# AfternoonCape_RevB1_TImux.net
KiCad netlist of a schematic drawn in Altium Designer
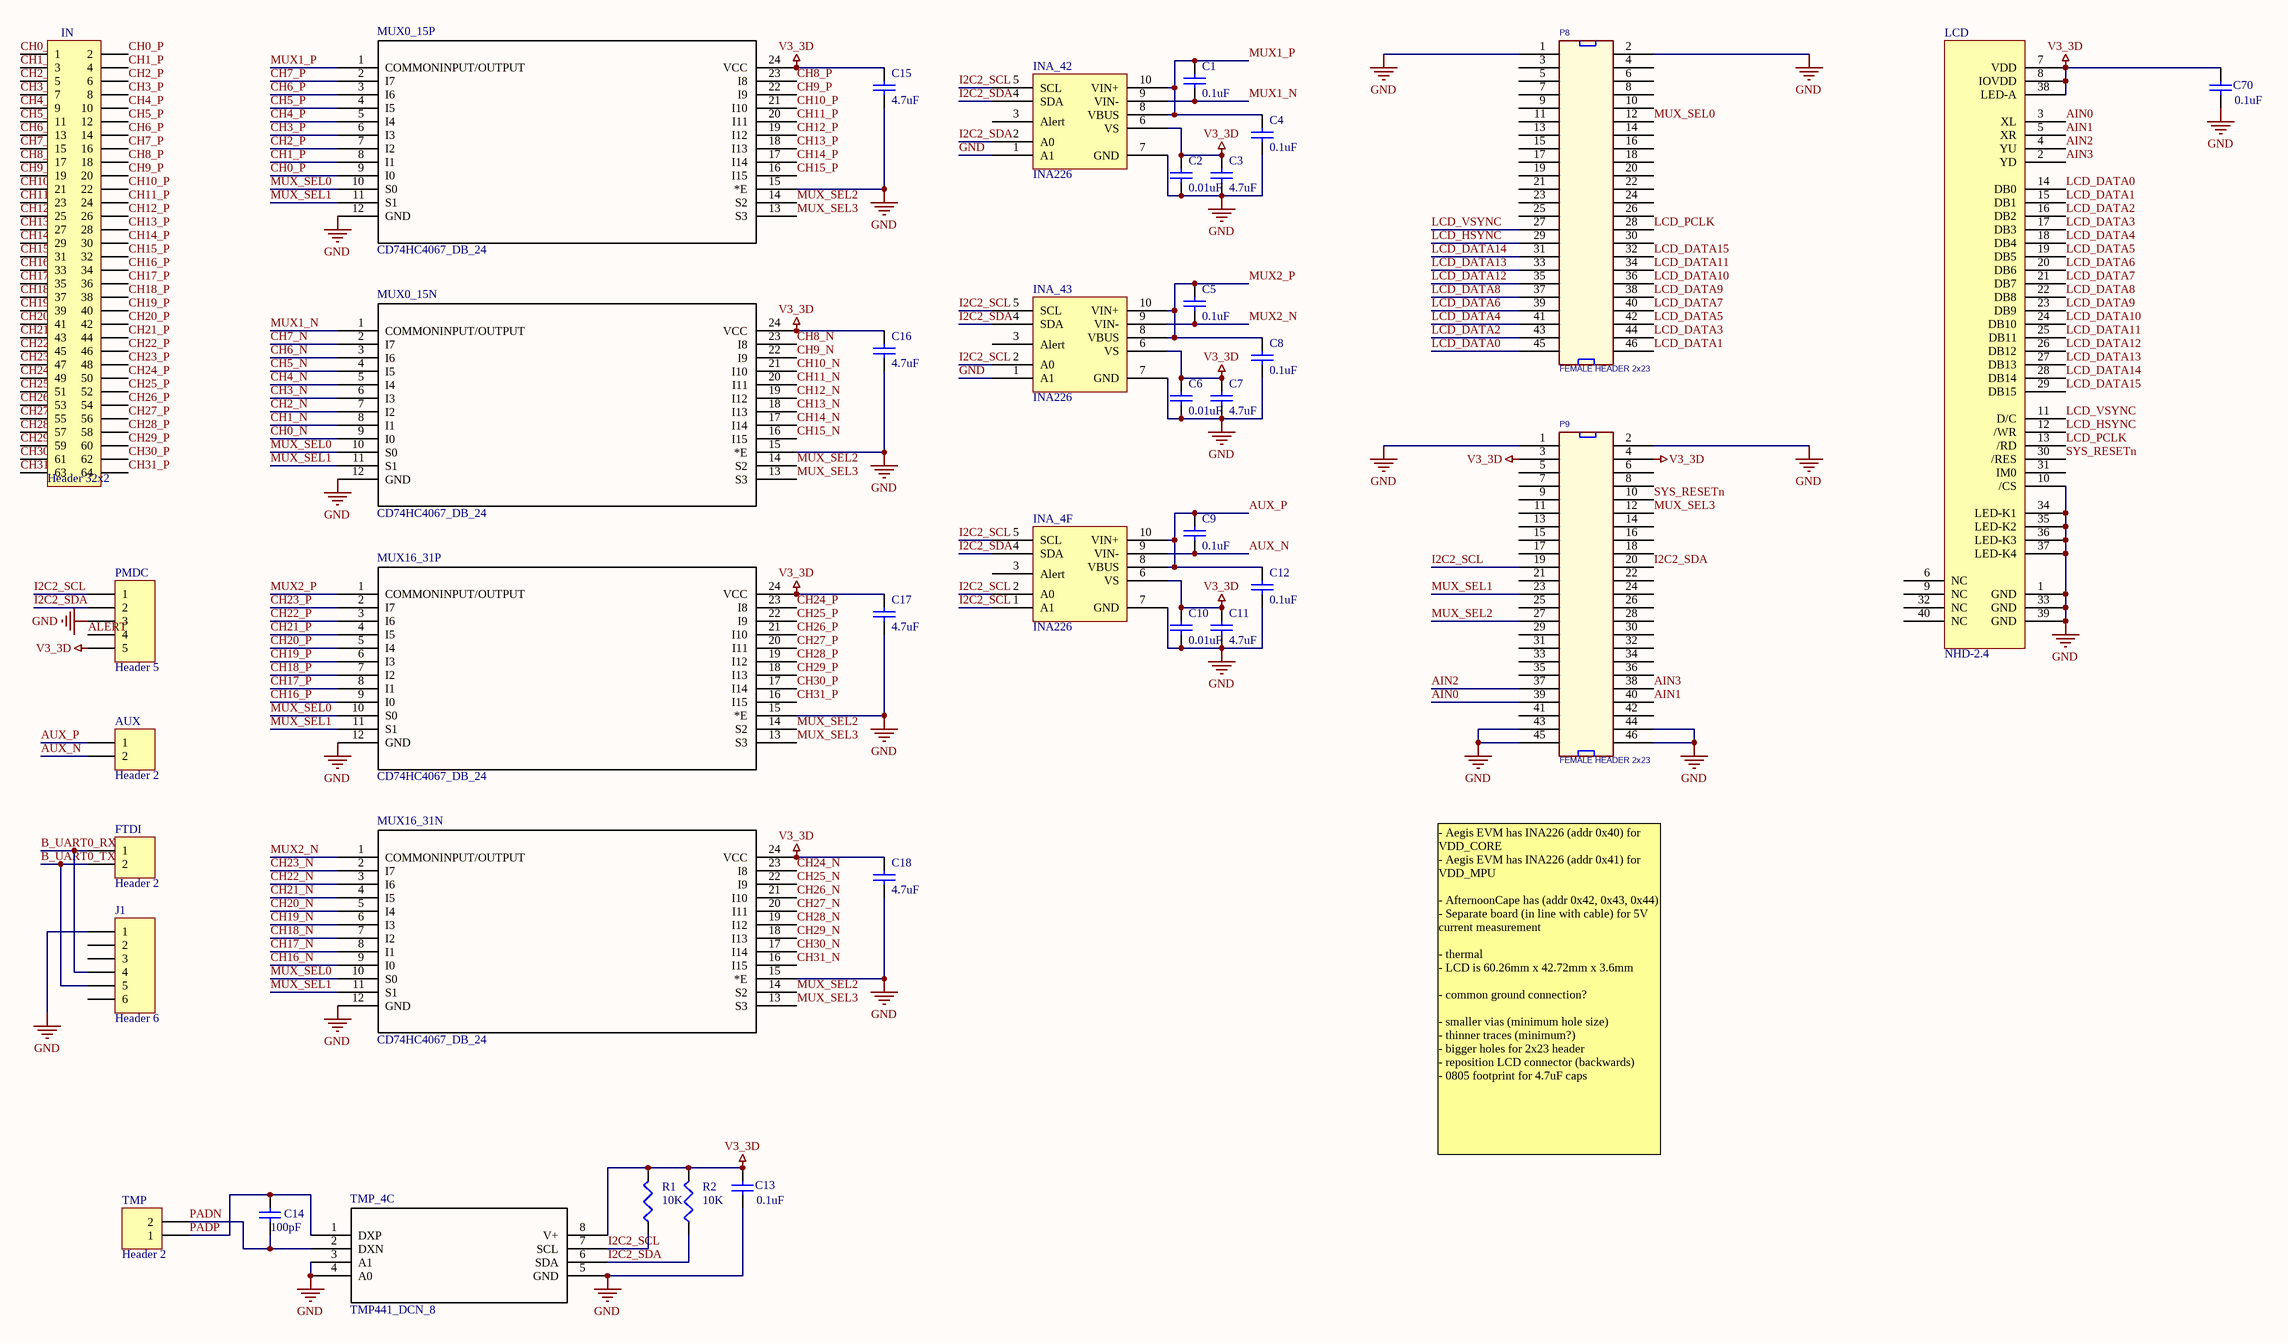
[diagram p0: AfternoonCape_RevB1_TImux.SchDoc]

(export (version "E")
  (design (tool "Eeschema 10.0.6"))
  (components
    (comp (ref "AUX")
      (value "Header 2")
      (footprint "HDR1X2")
      (description "Header, 2-Pin")
      (fields (field (name "PUBLISHER") "Altium Limited"))
      (libsource (lib "") (part "Header 2_1"))
    )
    (comp (ref "C1")
      (value "0.1uF")
      (footprint "0402")
      (description "Capacitor (Semiconductor SIM Model)")
      (fields (field (name "Comment") "Cap Semi") (field (name "PUBLISHER") "Altium Limited"))
      (libsource (lib "Miscellaneous Devices") (part "Cap Semi"))
    )
    (comp (ref "C2")
      (value "0.01uF")
      (footprint "0402")
      (description "Capacitor (Semiconductor SIM Model)")
      (fields (field (name "Comment") "Cap Semi") (field (name "PUBLISHER") "Altium Limited"))
      (libsource (lib "Miscellaneous Devices") (part "Cap Semi"))
    )
    (comp (ref "C3")
      (value "4.7uF")
      (footprint "C0805")
      (description "Capacitor (Semiconductor SIM Model)")
      (fields (field (name "Comment") "Cap Semi") (field (name "PUBLISHER") "Altium Limited"))
      (libsource (lib "Miscellaneous Devices") (part "Cap Semi"))
    )
    (comp (ref "C4")
      (value "0.1uF")
      (footprint "0402")
      (description "Capacitor (Semiconductor SIM Model)")
      (fields (field (name "Comment") "Cap Semi") (field (name "PUBLISHER") "Altium Limited"))
      (libsource (lib "Miscellaneous Devices") (part "Cap Semi"))
    )
    (comp (ref "C5")
      (value "0.1uF")
      (footprint "0402")
      (description "Capacitor (Semiconductor SIM Model)")
      (fields (field (name "Comment") "Cap Semi") (field (name "PUBLISHER") "Altium Limited"))
      (libsource (lib "Miscellaneous Devices") (part "Cap Semi"))
    )
    (comp (ref "C6")
      (value "0.01uF")
      (footprint "0402")
      (description "Capacitor (Semiconductor SIM Model)")
      (fields (field (name "Comment") "Cap Semi") (field (name "PUBLISHER") "Altium Limited"))
      (libsource (lib "Miscellaneous Devices") (part "Cap Semi"))
    )
    (comp (ref "C7")
      (value "4.7uF")
      (footprint "C0805")
      (description "Capacitor (Semiconductor SIM Model)")
      (fields (field (name "Comment") "Cap Semi") (field (name "PUBLISHER") "Altium Limited"))
      (libsource (lib "Miscellaneous Devices") (part "Cap Semi"))
    )
    (comp (ref "C8")
      (value "0.1uF")
      (footprint "0402")
      (description "Capacitor (Semiconductor SIM Model)")
      (fields (field (name "Comment") "Cap Semi") (field (name "PUBLISHER") "Altium Limited"))
      (libsource (lib "Miscellaneous Devices") (part "Cap Semi"))
    )
    (comp (ref "C9")
      (value "0.1uF")
      (footprint "0402")
      (description "Capacitor (Semiconductor SIM Model)")
      (fields (field (name "Comment") "Cap Semi") (field (name "PUBLISHER") "Altium Limited"))
      (libsource (lib "Miscellaneous Devices") (part "Cap Semi"))
    )
    (comp (ref "C10")
      (value "0.01uF")
      (footprint "0402")
      (description "Capacitor (Semiconductor SIM Model)")
      (fields (field (name "Comment") "Cap Semi") (field (name "PUBLISHER") "Altium Limited"))
      (libsource (lib "Miscellaneous Devices") (part "Cap Semi"))
    )
    (comp (ref "C11")
      (value "4.7uF")
      (footprint "C0805")
      (description "Capacitor (Semiconductor SIM Model)")
      (fields (field (name "Comment") "Cap Semi") (field (name "PUBLISHER") "Altium Limited"))
      (libsource (lib "Miscellaneous Devices") (part "Cap Semi"))
    )
    (comp (ref "C12")
      (value "0.1uF")
      (footprint "0402")
      (description "Capacitor (Semiconductor SIM Model)")
      (fields (field (name "Comment") "Cap Semi") (field (name "PUBLISHER") "Altium Limited"))
      (libsource (lib "Miscellaneous Devices") (part "Cap Semi"))
    )
    (comp (ref "C13")
      (value "0.1uF")
      (footprint "0402")
      (description "Capacitor (Semiconductor SIM Model)")
      (fields (field (name "Comment") "Cap Semi") (field (name "PUBLISHER") "Altium Limited"))
      (libsource (lib "Miscellaneous Devices") (part "Cap Semi"))
    )
    (comp (ref "C14")
      (value "100pF")
      (footprint "0402")
      (description "Capacitor (Semiconductor SIM Model)")
      (fields (field (name "Comment") "Cap Semi") (field (name "PUBLISHER") "Altium Limited"))
      (libsource (lib "Miscellaneous Devices") (part "Cap Semi"))
    )
    (comp (ref "C15")
      (value "4.7uF")
      (footprint "C0805")
      (description "Capacitor (Semiconductor SIM Model)")
      (fields (field (name "Comment") "Cap Semi") (field (name "PUBLISHER") "Altium Limited"))
      (libsource (lib "Miscellaneous Devices") (part "Cap Semi"))
    )
    (comp (ref "C16")
      (value "4.7uF")
      (footprint "C0805")
      (description "Capacitor (Semiconductor SIM Model)")
      (fields (field (name "Comment") "Cap Semi") (field (name "PUBLISHER") "Altium Limited"))
      (libsource (lib "Miscellaneous Devices") (part "Cap Semi"))
    )
    (comp (ref "C17")
      (value "4.7uF")
      (footprint "C0805")
      (description "Capacitor (Semiconductor SIM Model)")
      (fields (field (name "Comment") "Cap Semi") (field (name "PUBLISHER") "Altium Limited"))
      (libsource (lib "Miscellaneous Devices") (part "Cap Semi"))
    )
    (comp (ref "C18")
      (value "4.7uF")
      (footprint "C0805")
      (description "Capacitor (Semiconductor SIM Model)")
      (fields (field (name "Comment") "Cap Semi") (field (name "PUBLISHER") "Altium Limited"))
      (libsource (lib "Miscellaneous Devices") (part "Cap Semi"))
    )
    (comp (ref "C70")
      (value "0.1uF")
      (footprint "0402")
      (description "Capacitor (Semiconductor SIM Model)")
      (fields (field (name "Comment") "Cap Semi") (field (name "PUBLISHER") "Altium Limited"))
      (libsource (lib "Miscellaneous Devices") (part "Cap Semi"))
    )
    (comp (ref "FTDI")
      (value "Header 2")
      (footprint "HDR1X2")
      (description "Header, 2-Pin")
      (fields (field (name "PUBLISHER") "Altium Limited"))
      (libsource (lib "") (part "Header 2_1"))
    )
    (comp (ref "IN")
      (value "Header 32x2")
      (footprint "HDR2x32")
      (description "Header, 32-Pin, Dual row")
      (libsource (lib "Miscellaneous Connectors") (part "Header 32x2"))
    )
    (comp (ref "INA_4F") (value "INA226") (footprint "DGS10") (libsource (lib "INA226") (part "INA226")))
    (comp (ref "INA_42") (value "INA226") (footprint "DGS10") (libsource (lib "INA226") (part "INA226")))
    (comp (ref "INA_43") (value "INA226") (footprint "DGS10") (libsource (lib "INA226") (part "INA226")))
    (comp (ref "J1")
      (value "Header 6")
      (footprint "HDR1X6")
      (description "6-pin female header, long legs for FTDI-USB cable")
      (fields (field (name "PUBLISHER") "Altium Limited"))
      (libsource (lib "Miscellaneous Connectors") (part "Header 6"))
    )
    (comp (ref "LCD")
      (value "NHD-2.4")
      (footprint "NHD-2.4")
      (description "2.4\" LCD NHD-2.4-240320SF-CTXL#-FTN1 54132-4062 Molex LCD Connector Footprint")
      (libsource (lib "Sitara_PowerMonitorCape") (part "NHD-2.4"))
    )
    (comp (ref "MUX0_15N")
      (value "CD74HC4067_DB_24")
      (footprint "DB24")
      (description "Imported")
      (fields
        (field (name "MANUFACTURER") "Texas Instruments")
        (field (name "GENERIC_PART_NUMBER") "CD74HC4067")
      )
      (libsource (lib "CD74HC4067_DB") (part "CD74HC4067_DB_24"))
    )
    (comp (ref "MUX0_15P")
      (value "CD74HC4067_DB_24")
      (footprint "DB24")
      (description "Imported")
      (fields
        (field (name "MANUFACTURER") "Texas Instruments")
        (field (name "GENERIC_PART_NUMBER") "CD74HC4067")
      )
      (libsource (lib "CD74HC4067_DB") (part "CD74HC4067_DB_24"))
    )
    (comp (ref "MUX16_31N")
      (value "CD74HC4067_DB_24")
      (footprint "DB24")
      (description "Imported")
      (fields
        (field (name "MANUFACTURER") "Texas Instruments")
        (field (name "GENERIC_PART_NUMBER") "CD74HC4067")
      )
      (libsource (lib "CD74HC4067_DB") (part "CD74HC4067_DB_24"))
    )
    (comp (ref "MUX16_31P")
      (value "CD74HC4067_DB_24")
      (footprint "DB24")
      (description "Imported")
      (fields
        (field (name "MANUFACTURER") "Texas Instruments")
        (field (name "GENERIC_PART_NUMBER") "CD74HC4067")
      )
      (libsource (lib "CD74HC4067_DB") (part "CD74HC4067_DB_24"))
    )
    (comp (ref "P8")
      (value "FEMALE HEADER 2x23")
      (description "CONN HEADER FMAL 46PS.1\" DL GOLD")
      (fields
        (field (name "MANUFACTURER") "Sullins Connector Solutions")
        (field (name "MANUFACTURER PART NUMBER") "PPPC232LFBN-RC")
      )
      (libsource (lib "BEAGLEBONEBLACK_REV A5B") (part "HDR_46_F_2_0.1_0.1"))
    )
    (comp (ref "P9")
      (value "FEMALE HEADER 2x23")
      (description "CONN HEADER FMAL 46PS.1\" DL GOLD")
      (fields
        (field (name "MANUFACTURER") "Sullins Connector Solutions")
        (field (name "MANUFACTURER PART NUMBER") "PPPC232LFBN-RC")
      )
      (libsource (lib "BEAGLEBONEBLACK_REV A5B") (part "HDR_46_F_2_0.1_0.1"))
    )
    (comp (ref "PMDC")
      (value "Header 5")
      (footprint "HDR1X5")
      (description "Header, 5-Pin")
      (fields (field (name "PUBLISHER") "Altium Limited"))
      (libsource (lib "Miscellaneous Connectors") (part "Header 5"))
    )
    (comp (ref "R1")
      (value "10K")
      (footprint "0402")
      (description "Resistor")
      (fields (field (name "Comment") "Res3") (field (name "PUBLISHER") "Altium Limited"))
      (libsource (lib "Miscellaneous Devices") (part "Res3"))
    )
    (comp (ref "R2")
      (value "10K")
      (footprint "0402")
      (description "Resistor")
      (fields (field (name "Comment") "Res3") (field (name "PUBLISHER") "Altium Limited"))
      (libsource (lib "Miscellaneous Devices") (part "Res3"))
    )
    (comp (ref "TMP")
      (value "Header 2")
      (footprint "HDR1X2")
      (description "Header, 2-Pin")
      (fields (field (name "PUBLISHER") "Altium Limited"))
      (libsource (lib "Miscellaneous Connectors") (part "Header 2"))
    )
    (comp (ref "TMP_4C")
      (value "TMP441_DCN_8")
      (footprint "DCN8")
      (description "Imported")
      (fields
        (field (name "MANUFACTURER_PART_NUMBER") "tmp441_dcn_8")
        (field (name "GENERIC_PART_NUMBER") "TMP441")
      )
      (libsource (lib "TMP441") (part "TMP441_DCN_8"))
    )
  )
  (nets
    (net (code "1") (name "/AIN0") (class "Default")
      (node (ref "LCD") (pin "3") (pinfunction "XL_3") (pintype "passive"))
      (node (ref "P9") (pin "39") (pinfunction "20_39") (pintype "passive"))
    )
    (net (code "2") (name "/AIN1") (class "Default")
      (node (ref "LCD") (pin "5") (pinfunction "XR_5") (pintype "passive"))
      (node (ref "P9") (pin "40") (pinfunction "45_40") (pintype "passive"))
    )
    (net (code "3") (name "/AIN2") (class "Default")
      (node (ref "LCD") (pin "4") (pinfunction "YU_4") (pintype "passive"))
      (node (ref "P9") (pin "37") (pinfunction "19_37") (pintype "passive"))
    )
    (net (code "4") (name "/AIN3") (class "Default")
      (node (ref "LCD") (pin "2") (pinfunction "YD_2") (pintype "passive"))
      (node (ref "P9") (pin "38") (pinfunction "44_38") (pintype "passive"))
    )
    (net (code "5") (name "/ALERT") (class "Default")
      (node (ref "PMDC") (pin "4") (pinfunction "4_4") (pintype "passive"))
    )
    (net (code "6") (name "/AUX_N") (class "Default")
      (node (ref "AUX") (pin "2") (pinfunction "2_2") (pintype "passive"))
      (node (ref "C9") (pin "1") (pinfunction "1_1") (pintype "passive"))
      (node (ref "INA_4F") (pin "9") (pinfunction "VIN-_9") (pintype "passive"))
    )
    (net (code "7") (name "/AUX_P") (class "Default")
      (node (ref "AUX") (pin "1") (pinfunction "1_1") (pintype "passive"))
      (node (ref "C12") (pin "2") (pinfunction "2_2") (pintype "passive"))
      (node (ref "C9") (pin "2") (pinfunction "2_2") (pintype "passive"))
      (node (ref "INA_4F") (pin "10") (pinfunction "VIN+_10") (pintype "passive"))
      (node (ref "INA_4F") (pin "8") (pinfunction "VBUS_8") (pintype "passive"))
    )
    (net (code "8") (name "/B_UART0_RX") (class "Default")
      (node (ref "FTDI") (pin "1") (pinfunction "1_1") (pintype "passive"))
      (node (ref "J1") (pin "4") (pinfunction "4_4") (pintype "passive"))
    )
    (net (code "9") (name "/B_UART0_TX") (class "Default")
      (node (ref "FTDI") (pin "2") (pinfunction "2_2") (pintype "passive"))
      (node (ref "J1") (pin "5") (pinfunction "5_5") (pintype "passive"))
    )
    (net (code "10") (name "/CH0_N") (class "Default")
      (node (ref "IN") (pin "1") (pinfunction "1_1") (pintype "passive"))
      (node (ref "MUX0_15N") (pin "9") (pinfunction "I0_9") (pintype "passive"))
    )
    (net (code "11") (name "/CH0_P") (class "Default")
      (node (ref "IN") (pin "2") (pinfunction "2_2") (pintype "passive"))
      (node (ref "MUX0_15P") (pin "9") (pinfunction "I0_9") (pintype "passive"))
    )
    (net (code "12") (name "/CH1_N") (class "Default")
      (node (ref "IN") (pin "3") (pinfunction "3_3") (pintype "passive"))
      (node (ref "MUX0_15N") (pin "8") (pinfunction "I1_8") (pintype "passive"))
    )
    (net (code "13") (name "/CH1_P") (class "Default")
      (node (ref "IN") (pin "4") (pinfunction "4_4") (pintype "passive"))
      (node (ref "MUX0_15P") (pin "8") (pinfunction "I1_8") (pintype "passive"))
    )
    (net (code "14") (name "/CH2_N") (class "Default")
      (node (ref "IN") (pin "5") (pinfunction "5_5") (pintype "passive"))
      (node (ref "MUX0_15N") (pin "7") (pinfunction "I2_7") (pintype "passive"))
    )
    (net (code "15") (name "/CH2_P") (class "Default")
      (node (ref "IN") (pin "6") (pinfunction "6_6") (pintype "passive"))
      (node (ref "MUX0_15P") (pin "7") (pinfunction "I2_7") (pintype "passive"))
    )
    (net (code "16") (name "/CH3_N") (class "Default")
      (node (ref "IN") (pin "7") (pinfunction "7_7") (pintype "passive"))
      (node (ref "MUX0_15N") (pin "6") (pinfunction "I3_6") (pintype "passive"))
    )
    (net (code "17") (name "/CH3_P") (class "Default")
      (node (ref "IN") (pin "8") (pinfunction "8_8") (pintype "passive"))
      (node (ref "MUX0_15P") (pin "6") (pinfunction "I3_6") (pintype "passive"))
    )
    (net (code "18") (name "/CH4_N") (class "Default")
      (node (ref "IN") (pin "9") (pinfunction "9_9") (pintype "passive"))
      (node (ref "MUX0_15N") (pin "5") (pinfunction "I4_5") (pintype "passive"))
    )
    (net (code "19") (name "/CH4_P") (class "Default")
      (node (ref "IN") (pin "10") (pinfunction "10_10") (pintype "passive"))
      (node (ref "MUX0_15P") (pin "5") (pinfunction "I4_5") (pintype "passive"))
    )
    (net (code "20") (name "/CH5_N") (class "Default")
      (node (ref "IN") (pin "11") (pinfunction "11_11") (pintype "passive"))
      (node (ref "MUX0_15N") (pin "4") (pinfunction "I5_4") (pintype "passive"))
    )
    (net (code "21") (name "/CH5_P") (class "Default")
      (node (ref "IN") (pin "12") (pinfunction "12_12") (pintype "passive"))
      (node (ref "MUX0_15P") (pin "4") (pinfunction "I5_4") (pintype "passive"))
    )
    (net (code "22") (name "/CH6_N") (class "Default")
      (node (ref "IN") (pin "13") (pinfunction "13_13") (pintype "passive"))
      (node (ref "MUX0_15N") (pin "3") (pinfunction "I6_3") (pintype "passive"))
    )
    (net (code "23") (name "/CH6_P") (class "Default")
      (node (ref "IN") (pin "14") (pinfunction "14_14") (pintype "passive"))
      (node (ref "MUX0_15P") (pin "3") (pinfunction "I6_3") (pintype "passive"))
    )
    (net (code "24") (name "/CH7_N") (class "Default")
      (node (ref "IN") (pin "15") (pinfunction "15_15") (pintype "passive"))
      (node (ref "MUX0_15N") (pin "2") (pinfunction "I7_2") (pintype "passive"))
    )
    (net (code "25") (name "/CH7_P") (class "Default")
      (node (ref "IN") (pin "16") (pinfunction "16_16") (pintype "passive"))
      (node (ref "MUX0_15P") (pin "2") (pinfunction "I7_2") (pintype "passive"))
    )
    (net (code "26") (name "/CH8_N") (class "Default")
      (node (ref "IN") (pin "17") (pinfunction "17_17") (pintype "passive"))
      (node (ref "MUX0_15N") (pin "23") (pinfunction "I8_23") (pintype "passive"))
    )
    (net (code "27") (name "/CH8_P") (class "Default")
      (node (ref "IN") (pin "18") (pinfunction "18_18") (pintype "passive"))
      (node (ref "MUX0_15P") (pin "23") (pinfunction "I8_23") (pintype "passive"))
    )
    (net (code "28") (name "/CH9_N") (class "Default")
      (node (ref "IN") (pin "19") (pinfunction "19_19") (pintype "passive"))
      (node (ref "MUX0_15N") (pin "22") (pinfunction "I9_22") (pintype "passive"))
    )
    (net (code "29") (name "/CH9_P") (class "Default")
      (node (ref "IN") (pin "20") (pinfunction "20_20") (pintype "passive"))
      (node (ref "MUX0_15P") (pin "22") (pinfunction "I9_22") (pintype "passive"))
    )
    (net (code "30") (name "/CH10_N") (class "Default")
      (node (ref "IN") (pin "21") (pinfunction "21_21") (pintype "passive"))
      (node (ref "MUX0_15N") (pin "21") (pinfunction "I10_21") (pintype "passive"))
    )
    (net (code "31") (name "/CH10_P") (class "Default")
      (node (ref "IN") (pin "22") (pinfunction "22_22") (pintype "passive"))
      (node (ref "MUX0_15P") (pin "21") (pinfunction "I10_21") (pintype "passive"))
    )
    (net (code "32") (name "/CH11_N") (class "Default")
      (node (ref "IN") (pin "23") (pinfunction "23_23") (pintype "passive"))
      (node (ref "MUX0_15N") (pin "20") (pinfunction "I11_20") (pintype "passive"))
    )
    (net (code "33") (name "/CH11_P") (class "Default")
      (node (ref "IN") (pin "24") (pinfunction "24_24") (pintype "passive"))
      (node (ref "MUX0_15P") (pin "20") (pinfunction "I11_20") (pintype "passive"))
    )
    (net (code "34") (name "/CH12_N") (class "Default")
      (node (ref "IN") (pin "25") (pinfunction "25_25") (pintype "passive"))
      (node (ref "MUX0_15N") (pin "19") (pinfunction "I12_19") (pintype "passive"))
    )
    (net (code "35") (name "/CH12_P") (class "Default")
      (node (ref "IN") (pin "26") (pinfunction "26_26") (pintype "passive"))
      (node (ref "MUX0_15P") (pin "19") (pinfunction "I12_19") (pintype "passive"))
    )
    (net (code "36") (name "/CH13_N") (class "Default")
      (node (ref "IN") (pin "27") (pinfunction "27_27") (pintype "passive"))
      (node (ref "MUX0_15N") (pin "18") (pinfunction "I13_18") (pintype "passive"))
    )
    (net (code "37") (name "/CH13_P") (class "Default")
      (node (ref "IN") (pin "28") (pinfunction "28_28") (pintype "passive"))
      (node (ref "MUX0_15P") (pin "18") (pinfunction "I13_18") (pintype "passive"))
    )
    (net (code "38") (name "/CH14_N") (class "Default")
      (node (ref "IN") (pin "29") (pinfunction "29_29") (pintype "passive"))
      (node (ref "MUX0_15N") (pin "17") (pinfunction "I14_17") (pintype "passive"))
    )
    (net (code "39") (name "/CH14_P") (class "Default")
      (node (ref "IN") (pin "30") (pinfunction "30_30") (pintype "passive"))
      (node (ref "MUX0_15P") (pin "17") (pinfunction "I14_17") (pintype "passive"))
    )
    (net (code "40") (name "/CH15_N") (class "Default")
      (node (ref "IN") (pin "31") (pinfunction "31_31") (pintype "passive"))
      (node (ref "MUX0_15N") (pin "16") (pinfunction "I15_16") (pintype "passive"))
    )
    (net (code "41") (name "/CH15_P") (class "Default")
      (node (ref "IN") (pin "32") (pinfunction "32_32") (pintype "passive"))
      (node (ref "MUX0_15P") (pin "16") (pinfunction "I15_16") (pintype "passive"))
    )
    (net (code "42") (name "/CH16_N") (class "Default")
      (node (ref "IN") (pin "33") (pinfunction "33_33") (pintype "passive"))
      (node (ref "MUX16_31N") (pin "9") (pinfunction "I0_9") (pintype "passive"))
    )
    (net (code "43") (name "/CH16_P") (class "Default")
      (node (ref "IN") (pin "34") (pinfunction "34_34") (pintype "passive"))
      (node (ref "MUX16_31P") (pin "9") (pinfunction "I0_9") (pintype "passive"))
    )
    (net (code "44") (name "/CH17_N") (class "Default")
      (node (ref "IN") (pin "35") (pinfunction "35_35") (pintype "passive"))
      (node (ref "MUX16_31N") (pin "8") (pinfunction "I1_8") (pintype "passive"))
    )
    (net (code "45") (name "/CH17_P") (class "Default")
      (node (ref "IN") (pin "36") (pinfunction "36_36") (pintype "passive"))
      (node (ref "MUX16_31P") (pin "8") (pinfunction "I1_8") (pintype "passive"))
    )
    (net (code "46") (name "/CH18_N") (class "Default")
      (node (ref "IN") (pin "37") (pinfunction "37_37") (pintype "passive"))
      (node (ref "MUX16_31N") (pin "7") (pinfunction "I2_7") (pintype "passive"))
    )
    (net (code "47") (name "/CH18_P") (class "Default")
      (node (ref "IN") (pin "38") (pinfunction "38_38") (pintype "passive"))
      (node (ref "MUX16_31P") (pin "7") (pinfunction "I2_7") (pintype "passive"))
    )
    (net (code "48") (name "/CH19_N") (class "Default")
      (node (ref "IN") (pin "39") (pinfunction "39_39") (pintype "passive"))
      (node (ref "MUX16_31N") (pin "6") (pinfunction "I3_6") (pintype "passive"))
    )
    (net (code "49") (name "/CH19_P") (class "Default")
      (node (ref "IN") (pin "40") (pinfunction "40_40") (pintype "passive"))
      (node (ref "MUX16_31P") (pin "6") (pinfunction "I3_6") (pintype "passive"))
    )
    (net (code "50") (name "/CH20_N") (class "Default")
      (node (ref "IN") (pin "41") (pinfunction "41_41") (pintype "passive"))
      (node (ref "MUX16_31N") (pin "5") (pinfunction "I4_5") (pintype "passive"))
    )
    (net (code "51") (name "/CH20_P") (class "Default")
      (node (ref "IN") (pin "42") (pinfunction "42_42") (pintype "passive"))
      (node (ref "MUX16_31P") (pin "5") (pinfunction "I4_5") (pintype "passive"))
    )
    (net (code "52") (name "/CH21_N") (class "Default")
      (node (ref "IN") (pin "43") (pinfunction "43_43") (pintype "passive"))
      (node (ref "MUX16_31N") (pin "4") (pinfunction "I5_4") (pintype "passive"))
    )
    (net (code "53") (name "/CH21_P") (class "Default")
      (node (ref "IN") (pin "44") (pinfunction "44_44") (pintype "passive"))
      (node (ref "MUX16_31P") (pin "4") (pinfunction "I5_4") (pintype "passive"))
    )
    (net (code "54") (name "/CH22_N") (class "Default")
      (node (ref "IN") (pin "45") (pinfunction "45_45") (pintype "passive"))
      (node (ref "MUX16_31N") (pin "3") (pinfunction "I6_3") (pintype "passive"))
    )
    (net (code "55") (name "/CH22_P") (class "Default")
      (node (ref "IN") (pin "46") (pinfunction "46_46") (pintype "passive"))
      (node (ref "MUX16_31P") (pin "3") (pinfunction "I6_3") (pintype "passive"))
    )
    (net (code "56") (name "/CH23_N") (class "Default")
      (node (ref "IN") (pin "47") (pinfunction "47_47") (pintype "passive"))
      (node (ref "MUX16_31N") (pin "2") (pinfunction "I7_2") (pintype "passive"))
    )
    (net (code "57") (name "/CH23_P") (class "Default")
      (node (ref "IN") (pin "48") (pinfunction "48_48") (pintype "passive"))
      (node (ref "MUX16_31P") (pin "2") (pinfunction "I7_2") (pintype "passive"))
    )
    (net (code "58") (name "/CH24_N") (class "Default")
      (node (ref "IN") (pin "49") (pinfunction "49_49") (pintype "passive"))
      (node (ref "MUX16_31N") (pin "23") (pinfunction "I8_23") (pintype "passive"))
    )
    (net (code "59") (name "/CH24_P") (class "Default")
      (node (ref "IN") (pin "50") (pinfunction "50_50") (pintype "passive"))
      (node (ref "MUX16_31P") (pin "23") (pinfunction "I8_23") (pintype "passive"))
    )
    (net (code "60") (name "/CH25_N") (class "Default")
      (node (ref "IN") (pin "51") (pinfunction "51_51") (pintype "passive"))
      (node (ref "MUX16_31N") (pin "22") (pinfunction "I9_22") (pintype "passive"))
    )
    (net (code "61") (name "/CH25_P") (class "Default")
      (node (ref "IN") (pin "52") (pinfunction "52_52") (pintype "passive"))
      (node (ref "MUX16_31P") (pin "22") (pinfunction "I9_22") (pintype "passive"))
    )
    (net (code "62") (name "/CH26_N") (class "Default")
      (node (ref "IN") (pin "53") (pinfunction "53_53") (pintype "passive"))
      (node (ref "MUX16_31N") (pin "21") (pinfunction "I10_21") (pintype "passive"))
    )
    (net (code "63") (name "/CH26_P") (class "Default")
      (node (ref "IN") (pin "54") (pinfunction "54_54") (pintype "passive"))
      (node (ref "MUX16_31P") (pin "21") (pinfunction "I10_21") (pintype "passive"))
    )
    (net (code "64") (name "/CH27_N") (class "Default")
      (node (ref "IN") (pin "55") (pinfunction "55_55") (pintype "passive"))
      (node (ref "MUX16_31N") (pin "20") (pinfunction "I11_20") (pintype "passive"))
    )
    (net (code "65") (name "/CH27_P") (class "Default")
      (node (ref "IN") (pin "56") (pinfunction "56_56") (pintype "passive"))
      (node (ref "MUX16_31P") (pin "20") (pinfunction "I11_20") (pintype "passive"))
    )
    (net (code "66") (name "/CH28_N") (class "Default")
      (node (ref "IN") (pin "57") (pinfunction "57_57") (pintype "passive"))
      (node (ref "MUX16_31N") (pin "19") (pinfunction "I12_19") (pintype "passive"))
    )
    (net (code "67") (name "/CH28_P") (class "Default")
      (node (ref "IN") (pin "58") (pinfunction "58_58") (pintype "passive"))
      (node (ref "MUX16_31P") (pin "19") (pinfunction "I12_19") (pintype "passive"))
    )
    (net (code "68") (name "/CH29_N") (class "Default")
      (node (ref "IN") (pin "59") (pinfunction "59_59") (pintype "passive"))
      (node (ref "MUX16_31N") (pin "18") (pinfunction "I13_18") (pintype "passive"))
    )
    (net (code "69") (name "/CH29_P") (class "Default")
      (node (ref "IN") (pin "60") (pinfunction "60_60") (pintype "passive"))
      (node (ref "MUX16_31P") (pin "18") (pinfunction "I13_18") (pintype "passive"))
    )
    (net (code "70") (name "/CH30_N") (class "Default")
      (node (ref "IN") (pin "61") (pinfunction "61_61") (pintype "passive"))
      (node (ref "MUX16_31N") (pin "17") (pinfunction "I14_17") (pintype "passive"))
    )
    (net (code "71") (name "/CH30_P") (class "Default")
      (node (ref "IN") (pin "62") (pinfunction "62_62") (pintype "passive"))
      (node (ref "MUX16_31P") (pin "17") (pinfunction "I14_17") (pintype "passive"))
    )
    (net (code "72") (name "/CH31_N") (class "Default")
      (node (ref "IN") (pin "63") (pinfunction "63_63") (pintype "passive"))
      (node (ref "MUX16_31N") (pin "16") (pinfunction "I15_16") (pintype "passive"))
    )
    (net (code "73") (name "/CH31_P") (class "Default")
      (node (ref "IN") (pin "64") (pinfunction "64_64") (pintype "passive"))
      (node (ref "MUX16_31P") (pin "16") (pinfunction "I15_16") (pintype "passive"))
    )
    (net (code "74") (name "/I2C2_SCL") (class "Default")
      (node (ref "INA_42") (pin "5") (pinfunction "SCL_5") (pintype "passive"))
      (node (ref "INA_43") (pin "2") (pinfunction "A0_2") (pintype "passive"))
      (node (ref "INA_43") (pin "5") (pinfunction "SCL_5") (pintype "passive"))
      (node (ref "INA_4F") (pin "1") (pinfunction "A1_1") (pintype "passive"))
      (node (ref "INA_4F") (pin "2") (pinfunction "A0_2") (pintype "passive"))
      (node (ref "INA_4F") (pin "5") (pinfunction "SCL_5") (pintype "passive"))
      (node (ref "P9") (pin "19") (pinfunction "10_19") (pintype "passive"))
      (node (ref "PMDC") (pin "1") (pinfunction "1_1") (pintype "passive"))
      (node (ref "R1") (pin "1") (pinfunction "1_1") (pintype "passive"))
      (node (ref "TMP_4C") (pin "7") (pinfunction "SCL_7") (pintype "passive"))
    )
    (net (code "75") (name "/I2C2_SDA") (class "Default")
      (node (ref "INA_42") (pin "2") (pinfunction "A0_2") (pintype "passive"))
      (node (ref "INA_42") (pin "4") (pinfunction "SDA_4") (pintype "passive"))
      (node (ref "INA_43") (pin "4") (pinfunction "SDA_4") (pintype "passive"))
      (node (ref "INA_4F") (pin "4") (pinfunction "SDA_4") (pintype "passive"))
      (node (ref "P9") (pin "20") (pinfunction "35_20") (pintype "passive"))
      (node (ref "PMDC") (pin "2") (pinfunction "2_2") (pintype "passive"))
      (node (ref "R2") (pin "1") (pinfunction "1_1") (pintype "passive"))
      (node (ref "TMP_4C") (pin "6") (pinfunction "SDA_6") (pintype "passive"))
    )
    (net (code "76") (name "/LCD_DATA0") (class "Default")
      (node (ref "LCD") (pin "14") (pinfunction "DB0_14") (pintype "passive"))
      (node (ref "P8") (pin "45") (pinfunction "23_45") (pintype "passive"))
    )
    (net (code "77") (name "/LCD_DATA1") (class "Default")
      (node (ref "LCD") (pin "15") (pinfunction "DB1_15") (pintype "passive"))
      (node (ref "P8") (pin "46") (pinfunction "48_46") (pintype "passive"))
    )
    (net (code "78") (name "/LCD_DATA2") (class "Default")
      (node (ref "LCD") (pin "16") (pinfunction "DB2_16") (pintype "passive"))
      (node (ref "P8") (pin "43") (pinfunction "22_43") (pintype "passive"))
    )
    (net (code "79") (name "/LCD_DATA3") (class "Default")
      (node (ref "LCD") (pin "17") (pinfunction "DB3_17") (pintype "passive"))
      (node (ref "P8") (pin "44") (pinfunction "47_44") (pintype "passive"))
    )
    (net (code "80") (name "/LCD_DATA4") (class "Default")
      (node (ref "LCD") (pin "18") (pinfunction "DB4_18") (pintype "passive"))
      (node (ref "P8") (pin "41") (pinfunction "21_41") (pintype "passive"))
    )
    (net (code "81") (name "/LCD_DATA5") (class "Default")
      (node (ref "LCD") (pin "19") (pinfunction "DB5_19") (pintype "passive"))
      (node (ref "P8") (pin "42") (pinfunction "46_42") (pintype "passive"))
    )
    (net (code "82") (name "/LCD_DATA6") (class "Default")
      (node (ref "LCD") (pin "20") (pinfunction "DB6_20") (pintype "passive"))
      (node (ref "P8") (pin "39") (pinfunction "20_39") (pintype "passive"))
    )
    (net (code "83") (name "/LCD_DATA7") (class "Default")
      (node (ref "LCD") (pin "21") (pinfunction "DB7_21") (pintype "passive"))
      (node (ref "P8") (pin "40") (pinfunction "45_40") (pintype "passive"))
    )
    (net (code "84") (name "/LCD_DATA8") (class "Default")
      (node (ref "LCD") (pin "22") (pinfunction "DB8_22") (pintype "passive"))
      (node (ref "P8") (pin "37") (pinfunction "19_37") (pintype "passive"))
    )
    (net (code "85") (name "/LCD_DATA9") (class "Default")
      (node (ref "LCD") (pin "23") (pinfunction "DB9_23") (pintype "passive"))
      (node (ref "P8") (pin "38") (pinfunction "44_38") (pintype "passive"))
    )
    (net (code "86") (name "/LCD_DATA10") (class "Default")
      (node (ref "LCD") (pin "24") (pinfunction "DB10_24") (pintype "passive"))
      (node (ref "P8") (pin "36") (pinfunction "43_36") (pintype "passive"))
    )
    (net (code "87") (name "/LCD_DATA11") (class "Default")
      (node (ref "LCD") (pin "25") (pinfunction "DB11_25") (pintype "passive"))
      (node (ref "P8") (pin "34") (pinfunction "42_34") (pintype "passive"))
    )
    (net (code "88") (name "/LCD_DATA12") (class "Default")
      (node (ref "LCD") (pin "26") (pinfunction "DB12_26") (pintype "passive"))
      (node (ref "P8") (pin "35") (pinfunction "18_35") (pintype "passive"))
    )
    (net (code "89") (name "/LCD_DATA13") (class "Default")
      (node (ref "LCD") (pin "27") (pinfunction "DB13_27") (pintype "passive"))
      (node (ref "P8") (pin "33") (pinfunction "17_33") (pintype "passive"))
    )
    (net (code "90") (name "/LCD_DATA14") (class "Default")
      (node (ref "LCD") (pin "28") (pinfunction "DB14_28") (pintype "passive"))
      (node (ref "P8") (pin "31") (pinfunction "16_31") (pintype "passive"))
    )
    (net (code "91") (name "/LCD_DATA15") (class "Default")
      (node (ref "LCD") (pin "29") (pinfunction "DB15_29") (pintype "passive"))
      (node (ref "P8") (pin "32") (pinfunction "41_32") (pintype "passive"))
    )
    (net (code "92") (name "/LCD_HSYNC") (class "Default")
      (node (ref "LCD") (pin "12") (pinfunction "/WR_12") (pintype "passive"))
      (node (ref "P8") (pin "29") (pinfunction "15_29") (pintype "passive"))
    )
    (net (code "93") (name "/LCD_PCLK") (class "Default")
      (node (ref "LCD") (pin "13") (pinfunction "/RD_13") (pintype "passive"))
      (node (ref "P8") (pin "28") (pinfunction "39_28") (pintype "passive"))
    )
    (net (code "94") (name "/LCD_VSYNC") (class "Default")
      (node (ref "LCD") (pin "11") (pinfunction "D/C_11") (pintype "passive"))
      (node (ref "P8") (pin "27") (pinfunction "14_27") (pintype "passive"))
    )
    (net (code "95") (name "/MUX1_N") (class "Default")
      (node (ref "C1") (pin "1") (pinfunction "1_1") (pintype "passive"))
      (node (ref "INA_42") (pin "9") (pinfunction "VIN-_9") (pintype "passive"))
      (node (ref "MUX0_15N") (pin "1") (pinfunction "COMMONINPUT/OUTPUT_1") (pintype "passive"))
    )
    (net (code "96") (name "/MUX1_P") (class "Default")
      (node (ref "C1") (pin "2") (pinfunction "2_2") (pintype "passive"))
      (node (ref "C4") (pin "2") (pinfunction "2_2") (pintype "passive"))
      (node (ref "INA_42") (pin "10") (pinfunction "VIN+_10") (pintype "passive"))
      (node (ref "INA_42") (pin "8") (pinfunction "VBUS_8") (pintype "passive"))
      (node (ref "MUX0_15P") (pin "1") (pinfunction "COMMONINPUT/OUTPUT_1") (pintype "passive"))
    )
    (net (code "97") (name "/MUX2_N") (class "Default")
      (node (ref "C5") (pin "1") (pinfunction "1_1") (pintype "passive"))
      (node (ref "INA_43") (pin "9") (pinfunction "VIN-_9") (pintype "passive"))
      (node (ref "MUX16_31N") (pin "1") (pinfunction "COMMONINPUT/OUTPUT_1") (pintype "passive"))
    )
    (net (code "98") (name "/MUX2_P") (class "Default")
      (node (ref "C5") (pin "2") (pinfunction "2_2") (pintype "passive"))
      (node (ref "C8") (pin "2") (pinfunction "2_2") (pintype "passive"))
      (node (ref "INA_43") (pin "10") (pinfunction "VIN+_10") (pintype "passive"))
      (node (ref "INA_43") (pin "8") (pinfunction "VBUS_8") (pintype "passive"))
      (node (ref "MUX16_31P") (pin "1") (pinfunction "COMMONINPUT/OUTPUT_1") (pintype "passive"))
    )
    (net (code "99") (name "/MUX_SEL0") (class "Default")
      (node (ref "MUX0_15N") (pin "10") (pinfunction "S0_10") (pintype "passive"))
      (node (ref "MUX0_15P") (pin "10") (pinfunction "S0_10") (pintype "passive"))
      (node (ref "MUX16_31N") (pin "10") (pinfunction "S0_10") (pintype "passive"))
      (node (ref "MUX16_31P") (pin "10") (pinfunction "S0_10") (pintype "passive"))
      (node (ref "P8") (pin "12") (pinfunction "31_12") (pintype "passive"))
    )
    (net (code "100") (name "/MUX_SEL1") (class "Default")
      (node (ref "MUX0_15N") (pin "11") (pinfunction "S1_11") (pintype "passive"))
      (node (ref "MUX0_15P") (pin "11") (pinfunction "S1_11") (pintype "passive"))
      (node (ref "MUX16_31N") (pin "11") (pinfunction "S1_11") (pintype "passive"))
      (node (ref "MUX16_31P") (pin "11") (pinfunction "S1_11") (pintype "passive"))
      (node (ref "P9") (pin "23") (pinfunction "12_23") (pintype "passive"))
    )
    (net (code "101") (name "/MUX_SEL2") (class "Default")
      (node (ref "MUX0_15N") (pin "14") (pinfunction "S2_14") (pintype "passive"))
      (node (ref "MUX0_15P") (pin "14") (pinfunction "S2_14") (pintype "passive"))
      (node (ref "MUX16_31N") (pin "14") (pinfunction "S2_14") (pintype "passive"))
      (node (ref "MUX16_31P") (pin "14") (pinfunction "S2_14") (pintype "passive"))
      (node (ref "P9") (pin "27") (pinfunction "14_27") (pintype "passive"))
    )
    (net (code "102") (name "/MUX_SEL3") (class "Default")
      (node (ref "MUX0_15N") (pin "13") (pinfunction "S3_13") (pintype "passive"))
      (node (ref "MUX0_15P") (pin "13") (pinfunction "S3_13") (pintype "passive"))
      (node (ref "MUX16_31N") (pin "13") (pinfunction "S3_13") (pintype "passive"))
      (node (ref "MUX16_31P") (pin "13") (pinfunction "S3_13") (pintype "passive"))
      (node (ref "P9") (pin "12") (pinfunction "31_12") (pintype "passive"))
    )
    (net (code "103") (name "/PADN") (class "Default")
      (node (ref "C14") (pin "1") (pinfunction "1_1") (pintype "passive"))
      (node (ref "TMP") (pin "2") (pinfunction "2_2") (pintype "passive"))
      (node (ref "TMP_4C") (pin "2") (pinfunction "DXN_2") (pintype "passive"))
    )
    (net (code "104") (name "/PADP") (class "Default")
      (node (ref "C14") (pin "2") (pinfunction "2_2") (pintype "passive"))
      (node (ref "TMP") (pin "1") (pinfunction "1_1") (pintype "passive"))
      (node (ref "TMP_4C") (pin "1") (pinfunction "DXP_1") (pintype "passive"))
    )
    (net (code "105") (name "/SYS_RESETn") (class "Default")
      (node (ref "LCD") (pin "30") (pinfunction "/RES_30") (pintype "passive"))
      (node (ref "P9") (pin "10") (pinfunction "30_10") (pintype "passive"))
    )
    (net (code "106") (name "GND") (class "Default")
      (node (ref "C10") (pin "1") (pinfunction "1_1") (pintype "passive"))
      (node (ref "C11") (pin "1") (pinfunction "1_1") (pintype "passive"))
      (node (ref "C12") (pin "1") (pinfunction "1_1") (pintype "passive"))
      (node (ref "C13") (pin "1") (pinfunction "1_1") (pintype "passive"))
      (node (ref "C15") (pin "1") (pinfunction "1_1") (pintype "passive"))
      (node (ref "C16") (pin "1") (pinfunction "1_1") (pintype "passive"))
      (node (ref "C17") (pin "1") (pinfunction "1_1") (pintype "passive"))
      (node (ref "C18") (pin "1") (pinfunction "1_1") (pintype "passive"))
      (node (ref "C2") (pin "1") (pinfunction "1_1") (pintype "passive"))
      (node (ref "C3") (pin "1") (pinfunction "1_1") (pintype "passive"))
      (node (ref "C4") (pin "1") (pinfunction "1_1") (pintype "passive"))
      (node (ref "C6") (pin "1") (pinfunction "1_1") (pintype "passive"))
      (node (ref "C7") (pin "1") (pinfunction "1_1") (pintype "passive"))
      (node (ref "C70") (pin "1") (pinfunction "1_1") (pintype "passive"))
      (node (ref "C8") (pin "1") (pinfunction "1_1") (pintype "passive"))
      (node (ref "INA_42") (pin "1") (pinfunction "A1_1") (pintype "passive"))
      (node (ref "INA_42") (pin "7") (pinfunction "GND_7") (pintype "passive"))
      (node (ref "INA_43") (pin "1") (pinfunction "A1_1") (pintype "passive"))
      (node (ref "INA_43") (pin "7") (pinfunction "GND_7") (pintype "passive"))
      (node (ref "INA_4F") (pin "7") (pinfunction "GND_7") (pintype "passive"))
      (node (ref "J1") (pin "1") (pinfunction "1_1") (pintype "passive"))
      (node (ref "LCD") (pin "1") (pinfunction "GND_1") (pintype "passive"))
      (node (ref "LCD") (pin "10") (pinfunction "/CS_10") (pintype "passive"))
      (node (ref "LCD") (pin "33") (pinfunction "GND_33") (pintype "passive"))
      (node (ref "LCD") (pin "34") (pinfunction "LED-K1_34") (pintype "passive"))
      (node (ref "LCD") (pin "35") (pinfunction "LED-K2_35") (pintype "passive"))
      (node (ref "LCD") (pin "36") (pinfunction "LED-K3_36") (pintype "passive"))
      (node (ref "LCD") (pin "37") (pinfunction "LED-K4_37") (pintype "passive"))
      (node (ref "LCD") (pin "39") (pinfunction "GND_39") (pintype "passive"))
      (node (ref "MUX0_15N") (pin "12") (pinfunction "GND_12") (pintype "passive"))
      (node (ref "MUX0_15N") (pin "15") (pinfunction "*E_15") (pintype "passive"))
      (node (ref "MUX0_15P") (pin "12") (pinfunction "GND_12") (pintype "passive"))
      (node (ref "MUX0_15P") (pin "15") (pinfunction "*E_15") (pintype "passive"))
      (node (ref "MUX16_31N") (pin "12") (pinfunction "GND_12") (pintype "passive"))
      (node (ref "MUX16_31N") (pin "15") (pinfunction "*E_15") (pintype "passive"))
      (node (ref "MUX16_31P") (pin "12") (pinfunction "GND_12") (pintype "passive"))
      (node (ref "MUX16_31P") (pin "15") (pinfunction "*E_15") (pintype "passive"))
      (node (ref "P8") (pin "1") (pinfunction "1_1") (pintype "passive"))
      (node (ref "P8") (pin "2") (pinfunction "26_2") (pintype "passive"))
      (node (ref "P9") (pin "1") (pinfunction "1_1") (pintype "passive"))
      (node (ref "P9") (pin "2") (pinfunction "26_2") (pintype "passive"))
      (node (ref "P9") (pin "43") (pinfunction "22_43") (pintype "passive"))
      (node (ref "P9") (pin "44") (pinfunction "47_44") (pintype "passive"))
      (node (ref "P9") (pin "45") (pinfunction "23_45") (pintype "passive"))
      (node (ref "P9") (pin "46") (pinfunction "48_46") (pintype "passive"))
      (node (ref "PMDC") (pin "3") (pinfunction "3_3") (pintype "passive"))
      (node (ref "TMP_4C") (pin "3") (pinfunction "A1_3") (pintype "passive"))
      (node (ref "TMP_4C") (pin "4") (pinfunction "A0_4") (pintype "passive"))
      (node (ref "TMP_4C") (pin "5") (pinfunction "GND_5") (pintype "power_in"))
    )
    (net (code "107") (name "V3_3D") (class "Default")
      (node (ref "C10") (pin "2") (pinfunction "2_2") (pintype "passive"))
      (node (ref "C11") (pin "2") (pinfunction "2_2") (pintype "passive"))
      (node (ref "C13") (pin "2") (pinfunction "2_2") (pintype "passive"))
      (node (ref "C15") (pin "2") (pinfunction "2_2") (pintype "passive"))
      (node (ref "C16") (pin "2") (pinfunction "2_2") (pintype "passive"))
      (node (ref "C17") (pin "2") (pinfunction "2_2") (pintype "passive"))
      (node (ref "C18") (pin "2") (pinfunction "2_2") (pintype "passive"))
      (node (ref "C2") (pin "2") (pinfunction "2_2") (pintype "passive"))
      (node (ref "C3") (pin "2") (pinfunction "2_2") (pintype "passive"))
      (node (ref "C6") (pin "2") (pinfunction "2_2") (pintype "passive"))
      (node (ref "C7") (pin "2") (pinfunction "2_2") (pintype "passive"))
      (node (ref "C70") (pin "2") (pinfunction "2_2") (pintype "passive"))
      (node (ref "INA_42") (pin "6") (pinfunction "VS_6") (pintype "passive"))
      (node (ref "INA_43") (pin "6") (pinfunction "VS_6") (pintype "passive"))
      (node (ref "INA_4F") (pin "6") (pinfunction "VS_6") (pintype "passive"))
      (node (ref "LCD") (pin "38") (pinfunction "LED-A_38") (pintype "passive"))
      (node (ref "LCD") (pin "7") (pinfunction "VDD_7") (pintype "passive"))
      (node (ref "LCD") (pin "8") (pinfunction "IOVDD_8") (pintype "passive"))
      (node (ref "MUX0_15N") (pin "24") (pinfunction "VCC_24") (pintype "passive"))
      (node (ref "MUX0_15P") (pin "24") (pinfunction "VCC_24") (pintype "passive"))
      (node (ref "MUX16_31N") (pin "24") (pinfunction "VCC_24") (pintype "passive"))
      (node (ref "MUX16_31P") (pin "24") (pinfunction "VCC_24") (pintype "passive"))
      (node (ref "P9") (pin "3") (pinfunction "2_3") (pintype "passive"))
      (node (ref "P9") (pin "4") (pinfunction "27_4") (pintype "passive"))
      (node (ref "PMDC") (pin "5") (pinfunction "5_5") (pintype "passive"))
      (node (ref "R1") (pin "2") (pinfunction "2_2") (pintype "passive"))
      (node (ref "R2") (pin "2") (pinfunction "2_2") (pintype "passive"))
      (node (ref "TMP_4C") (pin "8") (pinfunction "V+_8") (pintype "power_in"))
    )
    (net (code "108") (name "unconnected-(INA_4F-Alert-Pad3)") (class "Default")
      (node (ref "INA_4F") (pin "3") (pinfunction "Alert_3") (pintype "passive"))
    )
    (net (code "109") (name "unconnected-(INA_42-Alert-Pad3)") (class "Default")
      (node (ref "INA_42") (pin "3") (pinfunction "Alert_3") (pintype "passive"))
    )
    (net (code "110") (name "unconnected-(INA_43-Alert-Pad3)") (class "Default")
      (node (ref "INA_43") (pin "3") (pinfunction "Alert_3") (pintype "passive"))
    )
    (net (code "111") (name "unconnected-(J1-Pad2)") (class "Default")
      (node (ref "J1") (pin "2") (pinfunction "2_2") (pintype "passive"))
    )
    (net (code "112") (name "unconnected-(J1-Pad3)") (class "Default")
      (node (ref "J1") (pin "3") (pinfunction "3_3") (pintype "passive"))
    )
    (net (code "113") (name "unconnected-(J1-Pad6)") (class "Default")
      (node (ref "J1") (pin "6") (pinfunction "6_6") (pintype "passive"))
    )
    (net (code "114") (name "unconnected-(LCD-IM0-Pad31)") (class "Default")
      (node (ref "LCD") (pin "31") (pinfunction "IM0_31") (pintype "passive"))
    )
    (net (code "115") (name "unconnected-(LCD-NC-Pad6)") (class "Default")
      (node (ref "LCD") (pin "6") (pinfunction "NC_6") (pintype "passive"))
    )
    (net (code "116") (name "unconnected-(LCD-NC-Pad9)") (class "Default")
      (node (ref "LCD") (pin "9") (pinfunction "NC_9") (pintype "passive"))
    )
    (net (code "117") (name "unconnected-(LCD-NC-Pad32)") (class "Default")
      (node (ref "LCD") (pin "32") (pinfunction "NC_32") (pintype "passive"))
    )
    (net (code "118") (name "unconnected-(LCD-NC-Pad40)") (class "Default")
      (node (ref "LCD") (pin "40") (pinfunction "NC_40") (pintype "passive"))
    )
    (net (code "119") (name "unconnected-(P8-2-Pad3)") (class "Default")
      (node (ref "P8") (pin "3") (pinfunction "2_3") (pintype "passive"))
    )
    (net (code "120") (name "unconnected-(P8-3-Pad5)") (class "Default")
      (node (ref "P8") (pin "5") (pinfunction "3_5") (pintype "passive"))
    )
    (net (code "121") (name "unconnected-(P8-4-Pad7)") (class "Default")
      (node (ref "P8") (pin "7") (pinfunction "4_7") (pintype "passive"))
    )
    (net (code "122") (name "unconnected-(P8-5-Pad9)") (class "Default")
      (node (ref "P8") (pin "9") (pinfunction "5_9") (pintype "passive"))
    )
    (net (code "123") (name "unconnected-(P8-6-Pad11)") (class "Default")
      (node (ref "P8") (pin "11") (pinfunction "6_11") (pintype "passive"))
    )
    (net (code "124") (name "unconnected-(P8-7-Pad13)") (class "Default")
      (node (ref "P8") (pin "13") (pinfunction "7_13") (pintype "passive"))
    )
    (net (code "125") (name "unconnected-(P8-8-Pad15)") (class "Default")
      (node (ref "P8") (pin "15") (pinfunction "8_15") (pintype "passive"))
    )
    (net (code "126") (name "unconnected-(P8-9-Pad17)") (class "Default")
      (node (ref "P8") (pin "17") (pinfunction "9_17") (pintype "passive"))
    )
    (net (code "127") (name "unconnected-(P8-10-Pad19)") (class "Default")
      (node (ref "P8") (pin "19") (pinfunction "10_19") (pintype "passive"))
    )
    (net (code "128") (name "unconnected-(P8-11-Pad21)") (class "Default")
      (node (ref "P8") (pin "21") (pinfunction "11_21") (pintype "passive"))
    )
    (net (code "129") (name "unconnected-(P8-12-Pad23)") (class "Default")
      (node (ref "P8") (pin "23") (pinfunction "12_23") (pintype "passive"))
    )
    (net (code "130") (name "unconnected-(P8-13-Pad25)") (class "Default")
      (node (ref "P8") (pin "25") (pinfunction "13_25") (pintype "passive"))
    )
    (net (code "131") (name "unconnected-(P8-27-Pad4)") (class "Default")
      (node (ref "P8") (pin "4") (pinfunction "27_4") (pintype "passive"))
    )
    (net (code "132") (name "unconnected-(P8-28-Pad6)") (class "Default")
      (node (ref "P8") (pin "6") (pinfunction "28_6") (pintype "passive"))
    )
    (net (code "133") (name "unconnected-(P8-29-Pad8)") (class "Default")
      (node (ref "P8") (pin "8") (pinfunction "29_8") (pintype "passive"))
    )
    (net (code "134") (name "unconnected-(P8-30-Pad10)") (class "Default")
      (node (ref "P8") (pin "10") (pinfunction "30_10") (pintype "passive"))
    )
    (net (code "135") (name "unconnected-(P8-32-Pad14)") (class "Default")
      (node (ref "P8") (pin "14") (pinfunction "32_14") (pintype "passive"))
    )
    (net (code "136") (name "unconnected-(P8-33-Pad16)") (class "Default")
      (node (ref "P8") (pin "16") (pinfunction "33_16") (pintype "passive"))
    )
    (net (code "137") (name "unconnected-(P8-34-Pad18)") (class "Default")
      (node (ref "P8") (pin "18") (pinfunction "34_18") (pintype "passive"))
    )
    (net (code "138") (name "unconnected-(P8-35-Pad20)") (class "Default")
      (node (ref "P8") (pin "20") (pinfunction "35_20") (pintype "passive"))
    )
    (net (code "139") (name "unconnected-(P8-36-Pad22)") (class "Default")
      (node (ref "P8") (pin "22") (pinfunction "36_22") (pintype "passive"))
    )
    (net (code "140") (name "unconnected-(P8-37-Pad24)") (class "Default")
      (node (ref "P8") (pin "24") (pinfunction "37_24") (pintype "passive"))
    )
    (net (code "141") (name "unconnected-(P8-38-Pad26)") (class "Default")
      (node (ref "P8") (pin "26") (pinfunction "38_26") (pintype "passive"))
    )
    (net (code "142") (name "unconnected-(P8-40-Pad30)") (class "Default")
      (node (ref "P8") (pin "30") (pinfunction "40_30") (pintype "passive"))
    )
    (net (code "143") (name "unconnected-(P9-3-Pad5)") (class "Default")
      (node (ref "P9") (pin "5") (pinfunction "3_5") (pintype "passive"))
    )
    (net (code "144") (name "unconnected-(P9-4-Pad7)") (class "Default")
      (node (ref "P9") (pin "7") (pinfunction "4_7") (pintype "passive"))
    )
    (net (code "145") (name "unconnected-(P9-5-Pad9)") (class "Default")
      (node (ref "P9") (pin "9") (pinfunction "5_9") (pintype "passive"))
    )
    (net (code "146") (name "unconnected-(P9-6-Pad11)") (class "Default")
      (node (ref "P9") (pin "11") (pinfunction "6_11") (pintype "passive"))
    )
    (net (code "147") (name "unconnected-(P9-7-Pad13)") (class "Default")
      (node (ref "P9") (pin "13") (pinfunction "7_13") (pintype "passive"))
    )
    (net (code "148") (name "unconnected-(P9-8-Pad15)") (class "Default")
      (node (ref "P9") (pin "15") (pinfunction "8_15") (pintype "passive"))
    )
    (net (code "149") (name "unconnected-(P9-9-Pad17)") (class "Default")
      (node (ref "P9") (pin "17") (pinfunction "9_17") (pintype "passive"))
    )
    (net (code "150") (name "unconnected-(P9-11-Pad21)") (class "Default")
      (node (ref "P9") (pin "21") (pinfunction "11_21") (pintype "passive"))
    )
    (net (code "151") (name "unconnected-(P9-13-Pad25)") (class "Default")
      (node (ref "P9") (pin "25") (pinfunction "13_25") (pintype "passive"))
    )
    (net (code "152") (name "unconnected-(P9-15-Pad29)") (class "Default")
      (node (ref "P9") (pin "29") (pinfunction "15_29") (pintype "passive"))
    )
    (net (code "153") (name "unconnected-(P9-16-Pad31)") (class "Default")
      (node (ref "P9") (pin "31") (pinfunction "16_31") (pintype "passive"))
    )
    (net (code "154") (name "unconnected-(P9-17-Pad33)") (class "Default")
      (node (ref "P9") (pin "33") (pinfunction "17_33") (pintype "passive"))
    )
    (net (code "155") (name "unconnected-(P9-18-Pad35)") (class "Default")
      (node (ref "P9") (pin "35") (pinfunction "18_35") (pintype "passive"))
    )
    (net (code "156") (name "unconnected-(P9-21-Pad41)") (class "Default")
      (node (ref "P9") (pin "41") (pinfunction "21_41") (pintype "passive"))
    )
    (net (code "157") (name "unconnected-(P9-28-Pad6)") (class "Default")
      (node (ref "P9") (pin "6") (pinfunction "28_6") (pintype "passive"))
    )
    (net (code "158") (name "unconnected-(P9-29-Pad8)") (class "Default")
      (node (ref "P9") (pin "8") (pinfunction "29_8") (pintype "passive"))
    )
    (net (code "159") (name "unconnected-(P9-32-Pad14)") (class "Default")
      (node (ref "P9") (pin "14") (pinfunction "32_14") (pintype "passive"))
    )
    (net (code "160") (name "unconnected-(P9-33-Pad16)") (class "Default")
      (node (ref "P9") (pin "16") (pinfunction "33_16") (pintype "passive"))
    )
    (net (code "161") (name "unconnected-(P9-34-Pad18)") (class "Default")
      (node (ref "P9") (pin "18") (pinfunction "34_18") (pintype "passive"))
    )
    (net (code "162") (name "unconnected-(P9-36-Pad22)") (class "Default")
      (node (ref "P9") (pin "22") (pinfunction "36_22") (pintype "passive"))
    )
    (net (code "163") (name "unconnected-(P9-37-Pad24)") (class "Default")
      (node (ref "P9") (pin "24") (pinfunction "37_24") (pintype "passive"))
    )
    (net (code "164") (name "unconnected-(P9-38-Pad26)") (class "Default")
      (node (ref "P9") (pin "26") (pinfunction "38_26") (pintype "passive"))
    )
    (net (code "165") (name "unconnected-(P9-39-Pad28)") (class "Default")
      (node (ref "P9") (pin "28") (pinfunction "39_28") (pintype "passive"))
    )
    (net (code "166") (name "unconnected-(P9-40-Pad30)") (class "Default")
      (node (ref "P9") (pin "30") (pinfunction "40_30") (pintype "passive"))
    )
    (net (code "167") (name "unconnected-(P9-41-Pad32)") (class "Default")
      (node (ref "P9") (pin "32") (pinfunction "41_32") (pintype "passive"))
    )
    (net (code "168") (name "unconnected-(P9-42-Pad34)") (class "Default")
      (node (ref "P9") (pin "34") (pinfunction "42_34") (pintype "passive"))
    )
    (net (code "169") (name "unconnected-(P9-43-Pad36)") (class "Default")
      (node (ref "P9") (pin "36") (pinfunction "43_36") (pintype "passive"))
    )
    (net (code "170") (name "unconnected-(P9-46-Pad42)") (class "Default")
      (node (ref "P9") (pin "42") (pinfunction "46_42") (pintype "passive"))
    )
  )
)
